# AIRDCL.net
KiCad netlist of a schematic drawn in EAGLE
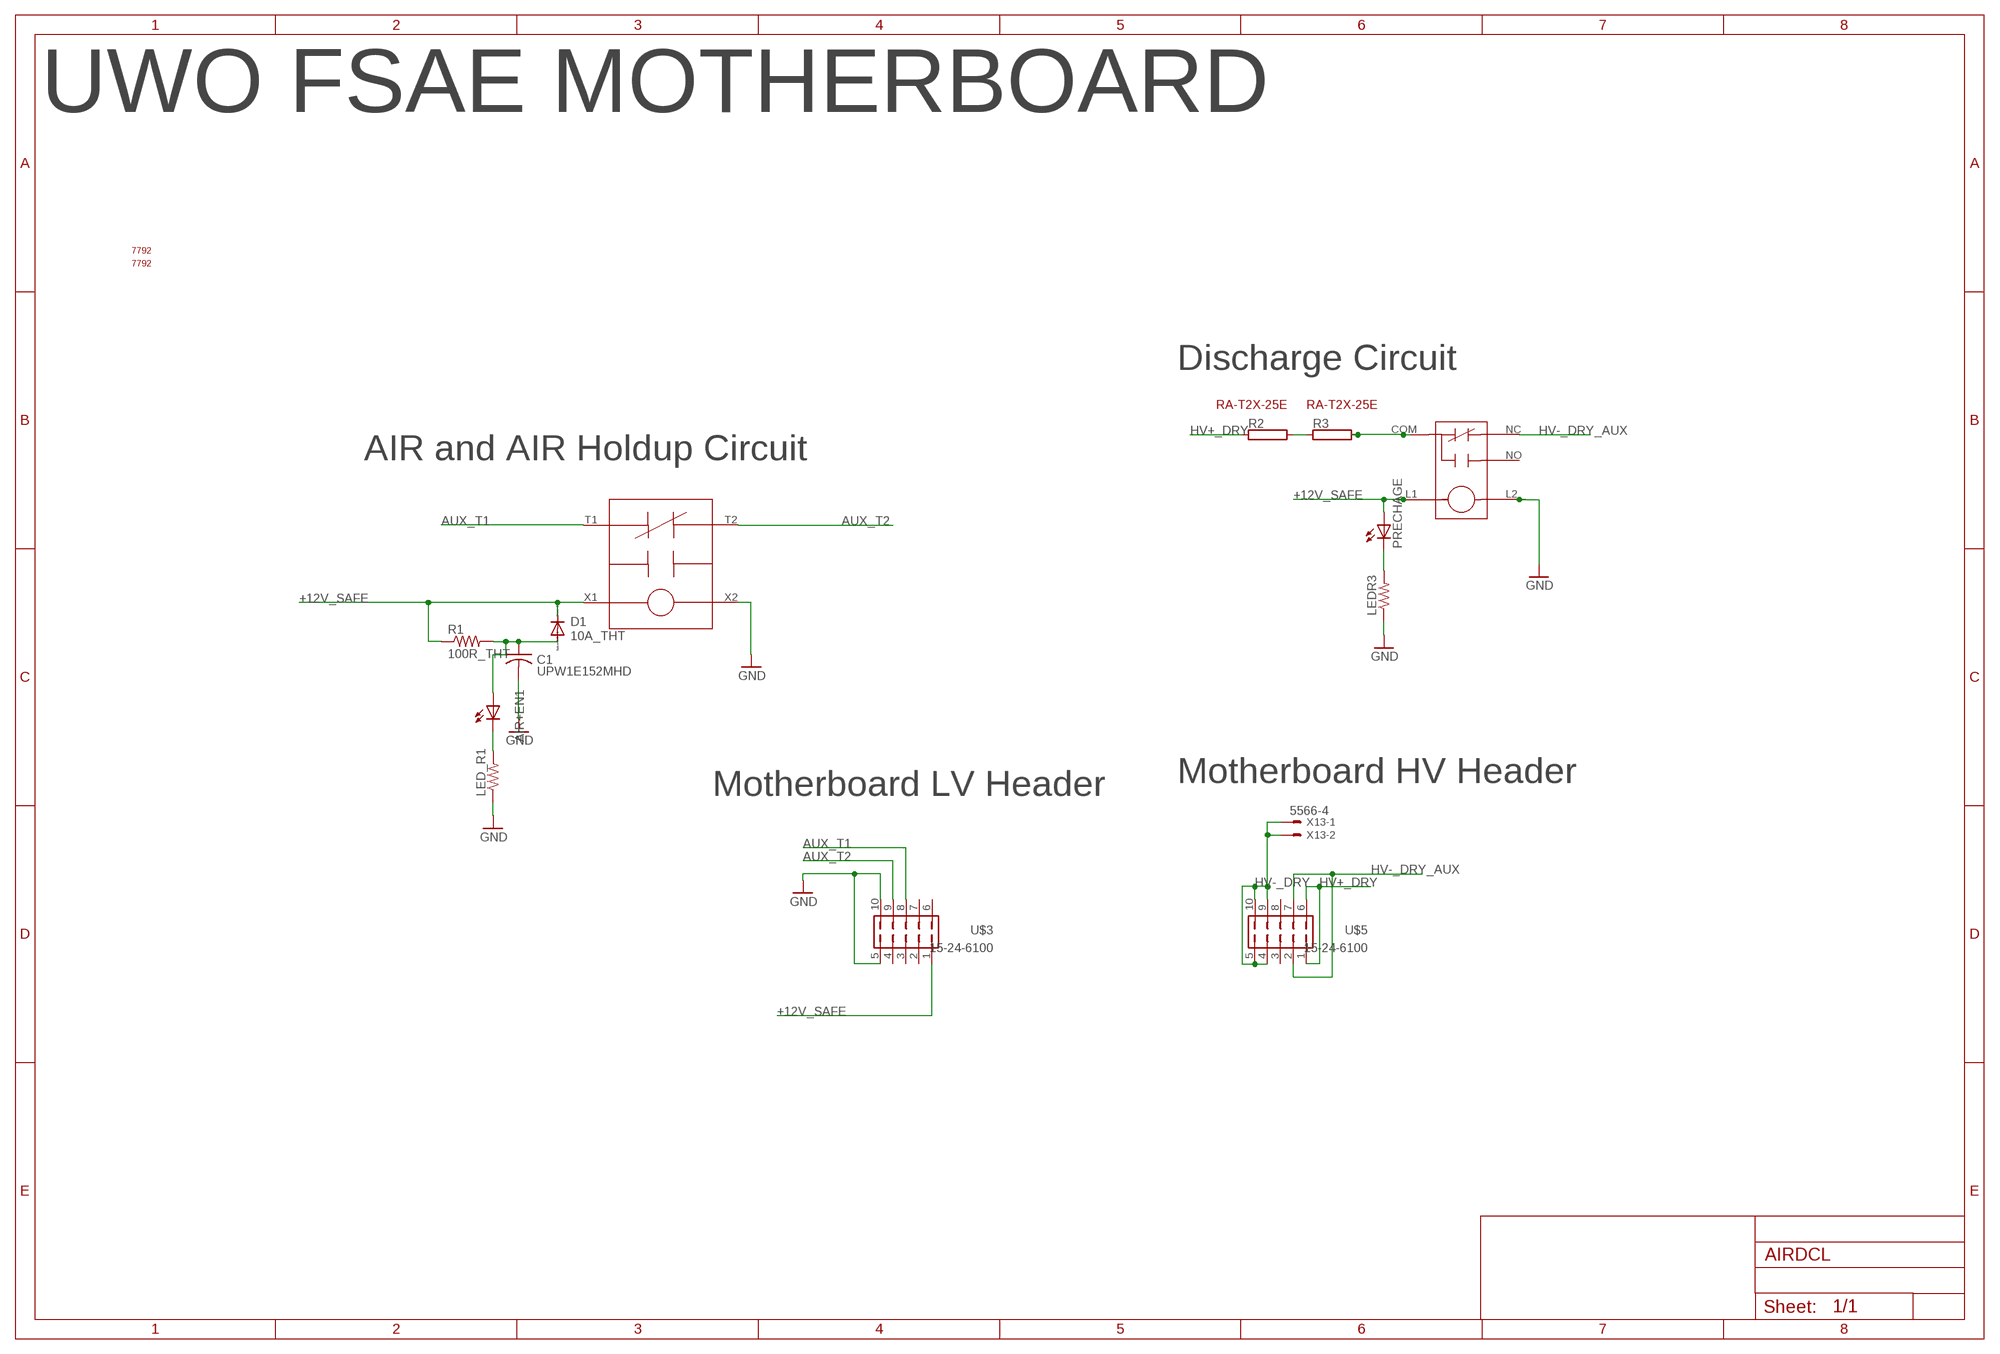
[diagram p0: schematic, sheet 1]

(export (version "E")
  (design (tool "Eeschema 10.0.6"))
  (components
    (comp (ref "AIR+EN1")
      (value "LEDCHIPLED_0805")
      (footprint "eagle-import:CHIPLED_0805")
      (libsource (lib "eagle-import") (part "LEDCHIPLED_0805"))
    )
    (comp (ref "C1")
      (value "UPW1E152MHD")
      (footprint "eagle-import:CAPPRD750W65D1800H3700B")
      (libsource (lib "eagle-import") (part "AIR_HOLDUP_CAP"))
    )
    (comp (ref "D1")
      (value "10A_THT")
      (footprint "eagle-import:DIOAD1570W120L850D500B")
      (libsource (lib "eagle-import") (part "AIR_HOLDUP_DIODE"))
    )
    (comp (ref "LEDR3")
      (value "R-US_R0805")
      (footprint "eagle-import:R0805")
      (libsource (lib "eagle-import") (part "R-US_R0805"))
    )
    (comp (ref "LED_R1")
      (value "R-US_R0805")
      (footprint "eagle-import:R0805")
      (libsource (lib "eagle-import") (part "R-US_R0805"))
    )
    (comp (ref "PRECHAGE")
      (value "LEDCHIPLED_0805")
      (footprint "eagle-import:CHIPLED_0805")
      (libsource (lib "eagle-import") (part "LEDCHIPLED_0805"))
    )
    (comp (ref "R1")
      (value "100R_THT")
      (footprint "eagle-import:RESAD976W63L650D250B")
      (libsource (lib "eagle-import") (part "AIR_HOLDUP_RESISTOR"))
    )
    (comp (ref "R2")
      (value "RMG100-V")
      (footprint "eagle-import:TO-247-2V")
      (libsource (lib "eagle-import") (part "RMG100-V"))
    )
    (comp (ref "R3")
      (value "RMG100-V")
      (footprint "eagle-import:TO-247-2V")
      (libsource (lib "eagle-import") (part "RMG100-V"))
    )
    (comp (ref "U$1")
      (value "GV245BPB")
      (footprint "eagle-import:GV224")
      (libsource (lib "eagle-import") (part "GV224"))
    )
    (comp (ref "U$2")
      (value "7792")
      (footprint "eagle-import:7792")
      (libsource (lib "eagle-import") (part "7792"))
    )
    (comp (ref "U$3")
      (value "15-24-6100")
      (footprint "eagle-import:15-24-6100")
      (libsource (lib "eagle-import") (part "15-24-6100"))
    )
    (comp (ref "U$4")
      (value "G81C335")
      (footprint "eagle-import:G81C335")
      (libsource (lib "eagle-import") (part "G81C335"))
    )
    (comp (ref "U$5")
      (value "15-24-6100")
      (footprint "eagle-import:15-24-6100")
      (libsource (lib "eagle-import") (part "15-24-6100"))
    )
    (comp (ref "U$6")
      (value "7792")
      (footprint "eagle-import:7792")
      (libsource (lib "eagle-import") (part "7792"))
    )
    (comp (ref "U$8")
      (value "RA-T2X-25E")
      (footprint "eagle-import:RA-T2X-25E")
      (libsource (lib "eagle-import") (part "RA-T2X-25E"))
    )
    (comp (ref "U$9")
      (value "RA-T2X-25E")
      (footprint "eagle-import:RA-T2X-25E")
      (libsource (lib "eagle-import") (part "RA-T2X-25E"))
    )
    (comp (ref "X13")
      (value "5566-4")
      (footprint "eagle-import:5566-4")
      (fields (field (name "MF") "MOLEX"))
      (libsource (lib "eagle-import") (part "5566-4"))
    )
  )
  (nets
    (net (code "1") (name "/+12V_SAFE") (class "Default")
      (node (ref "D1") (pin "1") (pinfunction "C_1") (pintype "passive"))
      (node (ref "PRECHAGE") (pin "A") (pinfunction "A_A") (pintype "passive"))
      (node (ref "R1") (pin "1") (pinfunction "1_1") (pintype "passive"))
      (node (ref "U$1") (pin "X1") (pinfunction "X1_X1") (pintype "bidirectional"))
      (node (ref "U$3") (pin "1") (pinfunction "1_1") (pintype "passive"))
      (node (ref "U$4") (pin "L1") (pinfunction "L1_L1") (pintype "bidirectional"))
    )
    (net (code "2") (name "/AUX_T1") (class "Default")
      (node (ref "U$1") (pin "T1") (pinfunction "T1_T1") (pintype "bidirectional"))
      (node (ref "U$3") (pin "8") (pinfunction "8_8") (pintype "passive"))
    )
    (net (code "3") (name "/AUX_T2") (class "Default")
      (node (ref "U$1") (pin "T2") (pinfunction "T2_T2") (pintype "bidirectional"))
      (node (ref "U$3") (pin "9") (pinfunction "9_9") (pintype "passive"))
    )
    (net (code "4") (name "/HV+_DRY") (class "Default")
      (node (ref "R2") (pin "1") (pinfunction "1_1") (pintype "passive"))
      (node (ref "U$5") (pin "1") (pinfunction "1_1") (pintype "passive"))
      (node (ref "U$5") (pin "6") (pinfunction "6_6") (pintype "passive"))
    )
    (net (code "5") (name "/HV-_DRY") (class "Default")
      (node (ref "U$5") (pin "10") (pinfunction "10_10") (pintype "passive"))
      (node (ref "U$5") (pin "4") (pinfunction "4_4") (pintype "passive"))
      (node (ref "U$5") (pin "5") (pinfunction "5_5") (pintype "passive"))
      (node (ref "U$5") (pin "9") (pinfunction "9_9") (pintype "passive"))
      (node (ref "X13") (pin "1") (pinfunction "S_1") (pintype "passive"))
      (node (ref "X13") (pin "2") (pinfunction "S_2") (pintype "passive"))
    )
    (net (code "6") (name "/HV-_DRY_AUX") (class "Default")
      (node (ref "U$4") (pin "NC") (pinfunction "NC_NC") (pintype "bidirectional"))
      (node (ref "U$5") (pin "2") (pinfunction "2_2") (pintype "passive"))
      (node (ref "U$5") (pin "7") (pinfunction "7_7") (pintype "passive"))
    )
    (net (code "7") (name "GND") (class "Default")
      (node (ref "C1") (pin "2") (pinfunction "2_2") (pintype "passive"))
      (node (ref "LEDR3") (pin "1") (pinfunction "1_1") (pintype "passive"))
      (node (ref "LED_R1") (pin "1") (pinfunction "1_1") (pintype "passive"))
      (node (ref "U$1") (pin "X2") (pinfunction "X2_X2") (pintype "bidirectional"))
      (node (ref "U$3") (pin "10") (pinfunction "10_10") (pintype "passive"))
      (node (ref "U$3") (pin "5") (pinfunction "5_5") (pintype "passive"))
      (node (ref "U$4") (pin "L2") (pinfunction "L2_L2") (pintype "bidirectional"))
    )
    (net (code "8") (name "Net-(AIR+EN1-PadC)") (class "Default")
      (node (ref "AIR+EN1") (pin "C") (pinfunction "C_C") (pintype "passive"))
      (node (ref "LED_R1") (pin "2") (pinfunction "2_2") (pintype "passive"))
    )
    (net (code "9") (name "Net-(D1-A)") (class "Default")
      (node (ref "AIR+EN1") (pin "A") (pinfunction "A_A") (pintype "passive"))
      (node (ref "C1") (pin "1") (pinfunction "1_1") (pintype "passive"))
      (node (ref "D1") (pin "2") (pinfunction "A_2") (pintype "passive"))
      (node (ref "R1") (pin "2") (pinfunction "2_2") (pintype "passive"))
    )
    (net (code "10") (name "Net-(LEDR3-Pad2)") (class "Default")
      (node (ref "LEDR3") (pin "2") (pinfunction "2_2") (pintype "passive"))
      (node (ref "PRECHAGE") (pin "C") (pinfunction "C_C") (pintype "passive"))
    )
    (net (code "11") (name "Net-(R2-Pad2)") (class "Default")
      (node (ref "R2") (pin "2") (pinfunction "2_2") (pintype "passive"))
      (node (ref "R3") (pin "1") (pinfunction "1_1") (pintype "passive"))
    )
    (net (code "12") (name "Net-(R3-Pad2)") (class "Default")
      (node (ref "R3") (pin "2") (pinfunction "2_2") (pintype "passive"))
      (node (ref "U$4") (pin "COM") (pinfunction "COM_COM") (pintype "bidirectional"))
    )
    (net (code "13") (name "unconnected-(U$3-Pad2)") (class "Default")
      (node (ref "U$3") (pin "2") (pinfunction "2_2") (pintype "passive"))
    )
    (net (code "14") (name "unconnected-(U$3-Pad3)") (class "Default")
      (node (ref "U$3") (pin "3") (pinfunction "3_3") (pintype "passive"))
    )
    (net (code "15") (name "unconnected-(U$3-Pad4)") (class "Default")
      (node (ref "U$3") (pin "4") (pinfunction "4_4") (pintype "passive"))
    )
    (net (code "16") (name "unconnected-(U$3-Pad6)") (class "Default")
      (node (ref "U$3") (pin "6") (pinfunction "6_6") (pintype "passive"))
    )
    (net (code "17") (name "unconnected-(U$3-Pad7)") (class "Default")
      (node (ref "U$3") (pin "7") (pinfunction "7_7") (pintype "passive"))
    )
    (net (code "18") (name "unconnected-(U$4-PadNO)") (class "Default")
      (node (ref "U$4") (pin "NO") (pinfunction "NO_NO") (pintype "bidirectional"))
    )
    (net (code "19") (name "unconnected-(U$5-Pad3)") (class "Default")
      (node (ref "U$5") (pin "3") (pinfunction "3_3") (pintype "passive"))
    )
    (net (code "20") (name "unconnected-(U$5-Pad8)") (class "Default")
      (node (ref "U$5") (pin "8") (pinfunction "8_8") (pintype "passive"))
    )
  )
)
